# mRo_CANnode_V1_R1.net
KiCad netlist of a schematic drawn in Altium Designer
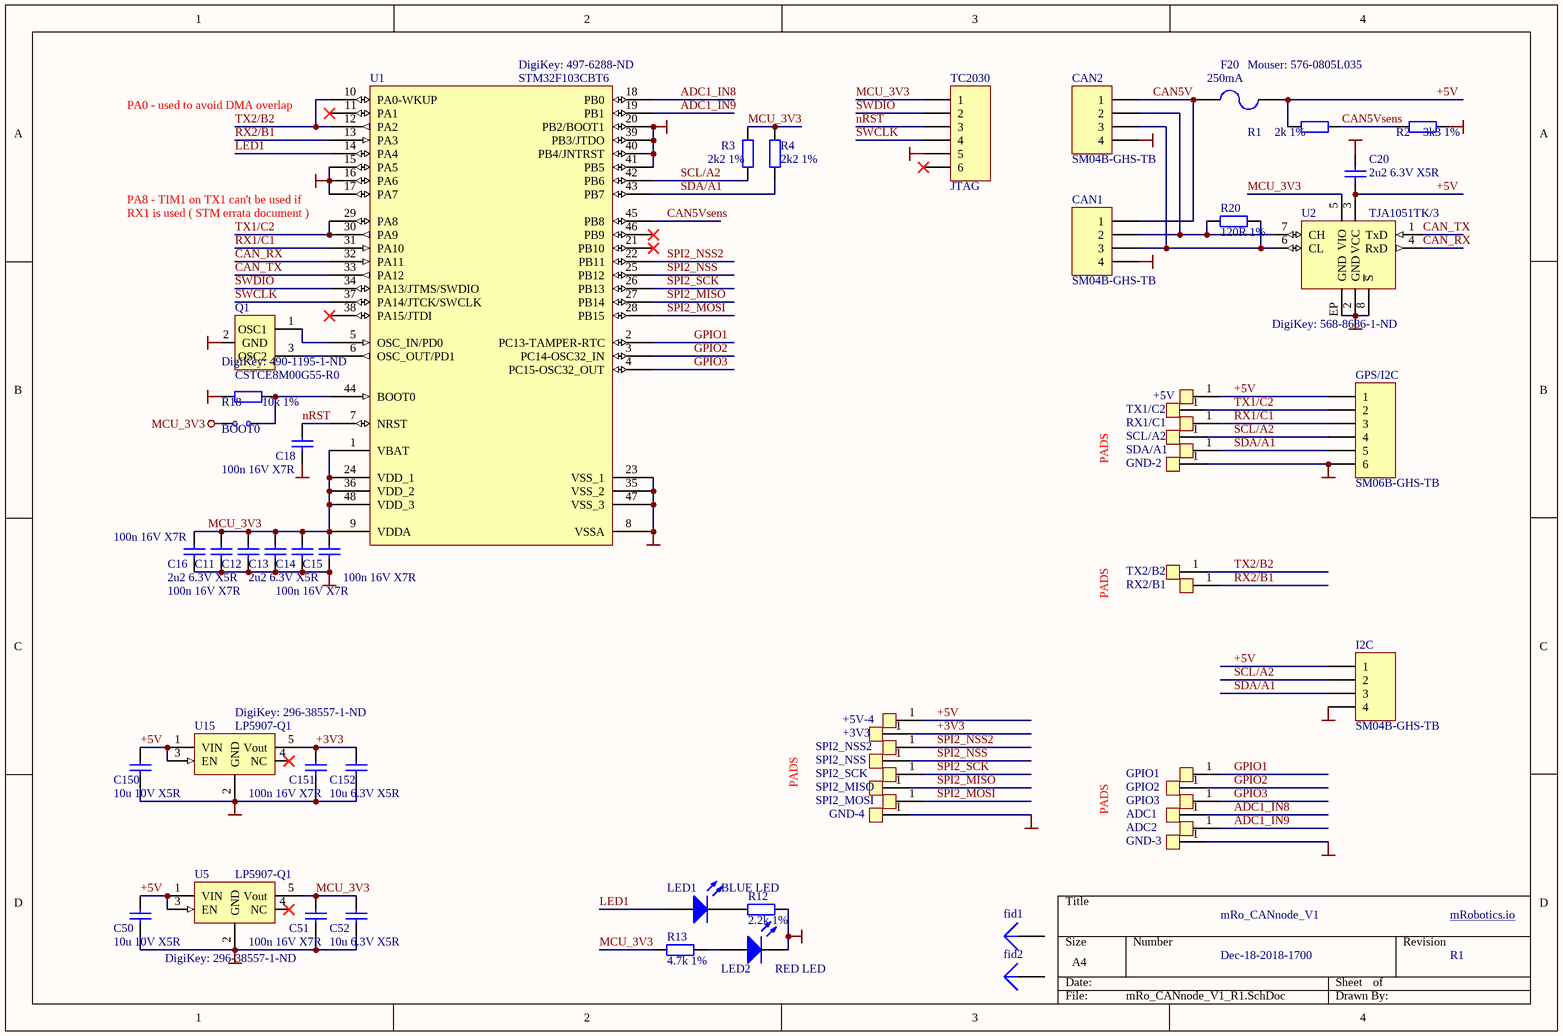
[diagram p0: mRo_CANnode_V1_R1.SchDoc]

(export (version "E")
  (design (tool "Eeschema 10.0.6"))
  (components
    (comp (ref "+3V3")
      (value "+5V")
      (footprint "SMD_TEST_PAD")
      (libsource (lib "My_Altium") (part "Test pad"))
    )
    (comp (ref "+5V")
      (value "+5V")
      (footprint "SMD_TEST_PAD")
      (libsource (lib "My_Altium") (part "Test pad"))
    )
    (comp (ref "+5V-4")
      (value "+5V")
      (footprint "SMD_TEST_PAD")
      (libsource (lib "My_Altium") (part "Test pad"))
    )
    (comp (ref "ADC1")
      (value "GND")
      (footprint "SMD_TEST_PAD")
      (libsource (lib "My_Altium") (part "Test pad"))
    )
    (comp (ref "ADC2")
      (value "GND")
      (footprint "SMD_TEST_PAD")
      (libsource (lib "My_Altium") (part "Test pad"))
    )
    (comp (ref "BOOT0") (value "BLOB") (footprint "BLOB 2") (libsource (lib "My_Altium") (part "BLOB")))
    (comp (ref "C11")
      (value "100n 16V X7R")
      (footprint "0402A")
      (description "Capacitor")
      (fields (field (name "PUBLISHER") "Altium Limited"))
      (libsource (lib "Miscellaneous Devices") (part "Cap"))
    )
    (comp (ref "C12")
      (value "2u2 6.3V X5R")
      (footprint "0402A")
      (description "Capacitor")
      (fields (field (name "PUBLISHER") "Altium Limited"))
      (libsource (lib "Miscellaneous Devices") (part "Cap"))
    )
    (comp (ref "C13")
      (value "2u2 6.3V X5R")
      (footprint "0402A")
      (description "Capacitor")
      (fields (field (name "PUBLISHER") "Altium Limited"))
      (libsource (lib "Miscellaneous Devices") (part "Cap"))
    )
    (comp (ref "C14")
      (value "100n 16V X7R")
      (footprint "0402A")
      (description "Capacitor")
      (fields (field (name "PUBLISHER") "Altium Limited"))
      (libsource (lib "Miscellaneous Devices") (part "Cap"))
    )
    (comp (ref "C15")
      (value "100n 16V X7R")
      (footprint "0402A")
      (description "Capacitor")
      (fields (field (name "PUBLISHER") "Altium Limited"))
      (libsource (lib "Miscellaneous Devices") (part "Cap"))
    )
    (comp (ref "C16")
      (value "100n 16V X7R")
      (footprint "0402A")
      (description "Capacitor")
      (fields (field (name "PUBLISHER") "Altium Limited"))
      (libsource (lib "Miscellaneous Devices") (part "Cap"))
    )
    (comp (ref "C18")
      (value "100n 16V X7R")
      (footprint "0402A")
      (description "Capacitor")
      (fields (field (name "PUBLISHER") "Altium Limited"))
      (libsource (lib "Miscellaneous Devices") (part "Cap"))
    )
    (comp (ref "C20")
      (value "2u2 6.3V X5R")
      (footprint "0402A")
      (description "Capacitor")
      (fields (field (name "PUBLISHER") "Altium Limited"))
      (libsource (lib "Miscellaneous Devices") (part "Cap"))
    )
    (comp (ref "C50")
      (value "10u 10V X5R")
      (footprint "0603A")
      (description "Capacitor")
      (fields (field (name "PUBLISHER") "Altium Limited"))
      (libsource (lib "Miscellaneous Devices") (part "Cap"))
    )
    (comp (ref "C51")
      (value "100n 16V X7R")
      (footprint "0603A")
      (description "Capacitor")
      (fields (field (name "PUBLISHER") "Altium Limited"))
      (libsource (lib "Miscellaneous Devices") (part "Cap"))
    )
    (comp (ref "C52")
      (value "10u 6.3V X5R")
      (footprint "0603A")
      (description "Capacitor")
      (fields (field (name "PUBLISHER") "Altium Limited"))
      (libsource (lib "Miscellaneous Devices") (part "Cap"))
    )
    (comp (ref "C150")
      (value "10u 10V X5R")
      (footprint "0603A")
      (description "Capacitor")
      (fields (field (name "PUBLISHER") "Altium Limited"))
      (libsource (lib "Miscellaneous Devices") (part "Cap"))
    )
    (comp (ref "C151")
      (value "100n 16V X7R")
      (footprint "0603A")
      (description "Capacitor")
      (fields (field (name "PUBLISHER") "Altium Limited"))
      (libsource (lib "Miscellaneous Devices") (part "Cap"))
    )
    (comp (ref "C152")
      (value "10u 6.3V X5R")
      (footprint "0603A")
      (description "Capacitor")
      (fields (field (name "PUBLISHER") "Altium Limited"))
      (libsource (lib "Miscellaneous Devices") (part "Cap"))
    )
    (comp (ref "CAN1")
      (value "SM04B-GHS-TB")
      (footprint "SM04B-GHS-TB")
      (description "Header, 4-Pin")
      (fields (field (name "PUBLISHER") "Altium Limited"))
      (libsource (lib "") (part "Header 4_1"))
    )
    (comp (ref "CAN2")
      (value "SM04B-GHS-TB")
      (footprint "SM04B-GHS-TB")
      (description "Header, 4-Pin")
      (fields (field (name "PUBLISHER") "Altium Limited"))
      (libsource (lib "") (part "Header 4_1"))
    )
    (comp (ref "F20")
      (value "250mA")
      (footprint "0805A")
      (description "Fuse")
      (fields
        (field (name "MANUFACTURER") "Generic Components")
        (field (name "MOUSER") "576-0805L035")
        (field (name "PUBLISHER") "Altium Hobart Technology Centre")
      )
      (libsource (lib "Miscellaneous Devices") (part "Fuse 2"))
    )
    (comp (ref "fid1")
      (value "~")
      (footprint "SMT_PAD")
      (description "Plug")
      (fields (field (name "PUBLISHER") "Altium Limited"))
      (libsource (lib "Miscellaneous Connectors") (part "Plug"))
    )
    (comp (ref "fid2")
      (value "~")
      (footprint "SMT_PAD")
      (description "Plug")
      (fields (field (name "PUBLISHER") "Altium Limited"))
      (libsource (lib "Miscellaneous Connectors") (part "Plug"))
    )
    (comp (ref "GND-2")
      (value "GND")
      (footprint "SMD_TEST_PAD")
      (libsource (lib "My_Altium") (part "Test pad"))
    )
    (comp (ref "GND-3")
      (value "GND")
      (footprint "SMD_TEST_PAD")
      (libsource (lib "My_Altium") (part "Test pad"))
    )
    (comp (ref "GND-4")
      (value "GND")
      (footprint "SMD_TEST_PAD")
      (libsource (lib "My_Altium") (part "Test pad"))
    )
    (comp (ref "GPIO1")
      (value "GPIO1")
      (footprint "SMD_TEST_PAD")
      (libsource (lib "My_Altium") (part "Test pad"))
    )
    (comp (ref "GPIO2")
      (value "GPIO2")
      (footprint "SMD_TEST_PAD")
      (libsource (lib "My_Altium") (part "Test pad"))
    )
    (comp (ref "GPIO3")
      (value "GPIO3")
      (footprint "SMD_TEST_PAD")
      (libsource (lib "My_Altium") (part "Test pad"))
    )
    (comp (ref "GPS/I2C")
      (value "SM06B-GHS-TB")
      (footprint "SM06B-GHS-TB")
      (description "Header, 6-Pin")
      (fields (field (name "PUBLISHER") "Altium Limited"))
      (libsource (lib "Miscellaneous Connectors") (part "Header 6"))
    )
    (comp (ref "I2C")
      (value "SM04B-GHS-TB")
      (footprint "SM04B-GHS-TB")
      (description "Header, 4-Pin")
      (fields (field (name "PUBLISHER") "Altium Limited"))
      (libsource (lib "Miscellaneous Connectors") (part "Header 4"))
    )
    (comp (ref "LED1")
      (value "BLUE LED")
      (footprint "0603A")
      (description "Typical INFRARED GaAs LED")
      (fields (field (name "PUBLISHER") "Altium Limited"))
      (libsource (lib "Miscellaneous Devices") (part "LED0"))
    )
    (comp (ref "LED2")
      (value "RED LED")
      (footprint "0603A")
      (description "Typical INFRARED GaAs LED")
      (fields (field (name "PUBLISHER") "Altium Limited"))
      (libsource (lib "Miscellaneous Devices") (part "LED0"))
    )
    (comp (ref "Q1")
      (value "CSTCE8M00G55-R0")
      (footprint "CERALOCK_RES")
      (fields (field (name "DIGIKEY") "490-1195-1-ND"))
      (libsource (lib "My_Altium") (part "CERAMIC_RESONATOR_3PIN"))
    )
    (comp (ref "R1")
      (value "2k 1%")
      (footprint "0402A")
      (description "Resistor")
      (fields (field (name "PUBLISHER") "Altium Limited"))
      (libsource (lib "Miscellaneous Devices") (part "Res2"))
    )
    (comp (ref "R2")
      (value "3k3 1%")
      (footprint "0402A")
      (description "Resistor")
      (fields (field (name "PUBLISHER") "Altium Limited"))
      (libsource (lib "Miscellaneous Devices") (part "Res2"))
    )
    (comp (ref "R3")
      (value "2k2 1%")
      (footprint "0402A")
      (description "Resistor")
      (fields (field (name "PUBLISHER") "Altium Limited"))
      (libsource (lib "") (part "Res2_1"))
    )
    (comp (ref "R4")
      (value "2k2 1%")
      (footprint "0402A")
      (description "Resistor")
      (fields (field (name "PUBLISHER") "Altium Limited"))
      (libsource (lib "") (part "Res2_1"))
    )
    (comp (ref "R12")
      (value "2.2k 1%")
      (footprint "0402A")
      (description "Resistor")
      (fields (field (name "PUBLISHER") "Altium Limited"))
      (libsource (lib "Miscellaneous Devices") (part "Res2"))
    )
    (comp (ref "R13")
      (value "4.7k 1%")
      (footprint "0603A")
      (description "Resistor")
      (fields (field (name "PUBLISHER") "Altium Limited"))
      (libsource (lib "Miscellaneous Devices") (part "Res2"))
    )
    (comp (ref "R18")
      (value "10k 1%")
      (footprint "0402A")
      (description "Resistor")
      (fields (field (name "PUBLISHER") "Altium Limited"))
      (libsource (lib "Miscellaneous Devices") (part "Res2"))
    )
    (comp (ref "R20")
      (value "120R 1%")
      (footprint "0603A")
      (description "Resistor")
      (fields (field (name "PUBLISHER") "Altium Limited"))
      (libsource (lib "Miscellaneous Devices") (part "Res2"))
    )
    (comp (ref "RX1/C1")
      (value "RX1/TLM/C1")
      (footprint "SMD_TEST_PAD")
      (libsource (lib "My_Altium") (part "Test pad"))
    )
    (comp (ref "RX2/B1")
      (value "RX2/B1")
      (footprint "SMD_TEST_PAD")
      (libsource (lib "My_Altium") (part "Test pad"))
    )
    (comp (ref "SCL/A2")
      (value "SDA")
      (footprint "SMD_TEST_PAD")
      (libsource (lib "My_Altium") (part "Test pad"))
    )
    (comp (ref "SDA/A1")
      (value "SDA/A1")
      (footprint "SMD_TEST_PAD")
      (libsource (lib "My_Altium") (part "Test pad"))
    )
    (comp (ref "SPI2_MISO")
      (value "SPI2_MISO")
      (footprint "SMD_TEST_PAD")
      (libsource (lib "My_Altium") (part "Test pad"))
    )
    (comp (ref "SPI2_MOSI")
      (value "SPI2_MOSI")
      (footprint "SMD_TEST_PAD")
      (libsource (lib "My_Altium") (part "Test pad"))
    )
    (comp (ref "SPI2_NSS")
      (value "SPI2_NSS")
      (footprint "SMD_TEST_PAD")
      (libsource (lib "My_Altium") (part "Test pad"))
    )
    (comp (ref "SPI2_NSS2")
      (value "SPI2_NSS2")
      (footprint "SMD_TEST_PAD")
      (libsource (lib "My_Altium") (part "Test pad"))
    )
    (comp (ref "SPI2_SCK")
      (value "SPI2_SCK")
      (footprint "SMD_TEST_PAD")
      (libsource (lib "My_Altium") (part "Test pad"))
    )
    (comp (ref "TC2030")
      (value "JTAG")
      (footprint "JTAG_TC2030")
      (description "Header, 6-Pin")
      (fields (field (name "PUBLISHER") "Altium Limited"))
      (libsource (lib "Miscellaneous Connectors") (part "Header 6"))
    )
    (comp (ref "TX1/C2")
      (value "VDD_USB")
      (footprint "SMD_TEST_PAD")
      (libsource (lib "My_Altium") (part "Test pad"))
    )
    (comp (ref "TX2/B2")
      (value "TX2/B2")
      (footprint "SMD_TEST_PAD")
      (libsource (lib "My_Altium") (part "Test pad"))
    )
    (comp (ref "U1")
      (value "STM32F103CBT6")
      (footprint "LQFP48_N")
      (description "STM32 ARM-based 32-bit MCU with 128 Kbytes Flash, 48-pin LQFP, Industrial Temperature")
      (fields (field (name "DIGIKEY") "497-6288-ND") (field (name "PUBLISHER") "Altium Limited"))
      (libsource (lib "ST Microcontroller 32-Bit STM32") (part "STM32F103CBT6"))
    )
    (comp (ref "U2")
      (value "TJA1051TK/3")
      (footprint "8DFN_3x3")
      (fields (field (name "DIGIKEY") "568-8686-1-ND"))
      (libsource (lib "My_Altium") (part "TJA1051T"))
    )
    (comp (ref "U5")
      (value "LP5907-Q1")
      (footprint "SOT23-5")
      (fields (field (name "DIGIKEY") "296-38557-1-ND"))
      (libsource (lib "My_Altium") (part "LP5907-Q1"))
    )
    (comp (ref "U15")
      (value "LP5907-Q1")
      (footprint "SOT23-5")
      (fields (field (name "DIGIKEY") "296-38557-1-ND"))
      (libsource (lib "My_Altium") (part "LP5907-Q1"))
    )
  )
  (nets
    (net (code "1") (name "/+3V3") (class "Default")
      (node (ref "+3V3") (pin "1") (pintype "passive"))
      (node (ref "C151") (pin "2") (pinfunction "2_2") (pintype "passive"))
      (node (ref "C152") (pin "2") (pinfunction "2_2") (pintype "passive"))
      (node (ref "U15") (pin "5") (pinfunction "Vout_5") (pintype "power_in"))
    )
    (net (code "2") (name "/+5V") (class "Default")
      (node (ref "+5V") (pin "1") (pintype "passive"))
      (node (ref "+5V-4") (pin "1") (pintype "passive"))
      (node (ref "C150") (pin "2") (pinfunction "2_2") (pintype "passive"))
      (node (ref "C20") (pin "2") (pinfunction "2_2") (pintype "passive"))
      (node (ref "C50") (pin "2") (pinfunction "2_2") (pintype "passive"))
      (node (ref "F20") (pin "2") (pinfunction "2_2") (pintype "passive"))
      (node (ref "GPS/I2C") (pin "1") (pinfunction "1_1") (pintype "passive"))
      (node (ref "I2C") (pin "1") (pinfunction "1_1") (pintype "passive"))
      (node (ref "R1") (pin "2") (pinfunction "2_2") (pintype "passive"))
      (node (ref "U15") (pin "1") (pinfunction "VIN_1") (pintype "power_in"))
      (node (ref "U15") (pin "3") (pinfunction "EN_3") (pintype "input"))
      (node (ref "U2") (pin "3") (pinfunction "VCC_3") (pintype "power_in"))
      (node (ref "U5") (pin "1") (pinfunction "VIN_1") (pintype "power_in"))
      (node (ref "U5") (pin "3") (pinfunction "EN_3") (pintype "input"))
    )
    (net (code "3") (name "/ADC1_IN8") (class "Default")
      (node (ref "ADC1") (pin "1") (pintype "passive"))
      (node (ref "U1") (pin "18") (pinfunction "PB0_18") (pintype "bidirectional"))
    )
    (net (code "4") (name "/ADC1_IN9") (class "Default")
      (node (ref "ADC2") (pin "1") (pintype "passive"))
      (node (ref "U1") (pin "19") (pinfunction "PB1_19") (pintype "bidirectional"))
    )
    (net (code "5") (name "/CAN5V") (class "Default")
      (node (ref "CAN1") (pin "1") (pinfunction "1_1") (pintype "passive"))
      (node (ref "CAN2") (pin "1") (pinfunction "1_1") (pintype "passive"))
      (node (ref "F20") (pin "1") (pinfunction "1_1") (pintype "passive"))
    )
    (net (code "6") (name "/CAN5Vsens") (class "Default")
      (node (ref "R1") (pin "1") (pinfunction "1_1") (pintype "passive"))
      (node (ref "R2") (pin "2") (pinfunction "2_2") (pintype "passive"))
      (node (ref "U1") (pin "45") (pinfunction "PB8_45") (pintype "bidirectional"))
    )
    (net (code "7") (name "/CAN_RX") (class "Default")
      (node (ref "U1") (pin "32") (pinfunction "PA11_32") (pintype "input"))
      (node (ref "U2") (pin "4") (pinfunction "RxD_4") (pintype "output"))
    )
    (net (code "8") (name "/CAN_TX") (class "Default")
      (node (ref "U1") (pin "33") (pinfunction "PA12_33") (pintype "output"))
      (node (ref "U2") (pin "1") (pinfunction "TxD_1") (pintype "input"))
    )
    (net (code "9") (name "/GPIO1") (class "Default")
      (node (ref "GPIO1") (pin "1") (pintype "passive"))
      (node (ref "U1") (pin "2") (pinfunction "PC13-TAMPER-RTC_2") (pintype "bidirectional"))
    )
    (net (code "10") (name "/GPIO2") (class "Default")
      (node (ref "GPIO2") (pin "1") (pintype "passive"))
      (node (ref "U1") (pin "3") (pinfunction "PC14-OSC32_IN_3") (pintype "bidirectional"))
    )
    (net (code "11") (name "/GPIO3") (class "Default")
      (node (ref "GPIO3") (pin "1") (pintype "passive"))
      (node (ref "U1") (pin "4") (pinfunction "PC15-OSC32_OUT_4") (pintype "bidirectional"))
    )
    (net (code "12") (name "/LED1") (class "Default")
      (node (ref "LED1") (pin "1") (pinfunction "A_1") (pintype "passive"))
      (node (ref "U1") (pin "14") (pinfunction "PA4_14") (pintype "bidirectional"))
    )
    (net (code "13") (name "/RX1{slash}C1") (class "Default")
      (node (ref "GPS/I2C") (pin "3") (pinfunction "3_3") (pintype "passive"))
      (node (ref "RX1/C1") (pin "1") (pintype "passive"))
      (node (ref "U1") (pin "31") (pinfunction "PA10_31") (pintype "input"))
    )
    (net (code "14") (name "/RX2{slash}B1") (class "Default")
      (node (ref "RX2/B1") (pin "1") (pintype "passive"))
      (node (ref "U1") (pin "13") (pinfunction "PA3_13") (pintype "input"))
    )
    (net (code "15") (name "/SCL{slash}A2") (class "Default")
      (node (ref "GPS/I2C") (pin "4") (pinfunction "4_4") (pintype "passive"))
      (node (ref "I2C") (pin "2") (pinfunction "2_2") (pintype "passive"))
      (node (ref "R3") (pin "2") (pinfunction "2_2") (pintype "passive"))
      (node (ref "SCL/A2") (pin "1") (pintype "passive"))
      (node (ref "U1") (pin "42") (pinfunction "PB6_42") (pintype "bidirectional"))
    )
    (net (code "16") (name "/SDA{slash}A1") (class "Default")
      (node (ref "GPS/I2C") (pin "5") (pinfunction "5_5") (pintype "passive"))
      (node (ref "I2C") (pin "3") (pinfunction "3_3") (pintype "passive"))
      (node (ref "R4") (pin "2") (pinfunction "2_2") (pintype "passive"))
      (node (ref "SDA/A1") (pin "1") (pintype "passive"))
      (node (ref "U1") (pin "43") (pinfunction "PB7_43") (pintype "bidirectional"))
    )
    (net (code "17") (name "/SPI2_MISO") (class "Default")
      (node (ref "SPI2_MISO") (pin "1") (pintype "passive"))
      (node (ref "U1") (pin "27") (pinfunction "PB14_27") (pintype "bidirectional"))
    )
    (net (code "18") (name "/SPI2_MOSI") (class "Default")
      (node (ref "SPI2_MOSI") (pin "1") (pintype "passive"))
      (node (ref "U1") (pin "28") (pinfunction "PB15_28") (pintype "bidirectional"))
    )
    (net (code "19") (name "/SPI2_NSS") (class "Default")
      (node (ref "SPI2_NSS") (pin "1") (pintype "passive"))
      (node (ref "U1") (pin "25") (pinfunction "PB12_25") (pintype "bidirectional"))
    )
    (net (code "20") (name "/SPI2_NSS2") (class "Default")
      (node (ref "SPI2_NSS2") (pin "1") (pintype "passive"))
      (node (ref "U1") (pin "22") (pinfunction "PB11_22") (pintype "bidirectional"))
    )
    (net (code "21") (name "/SPI2_SCK") (class "Default")
      (node (ref "SPI2_SCK") (pin "1") (pintype "passive"))
      (node (ref "U1") (pin "26") (pinfunction "PB13_26") (pintype "bidirectional"))
    )
    (net (code "22") (name "/SWCLK") (class "Default")
      (node (ref "TC2030") (pin "4") (pinfunction "4_4") (pintype "passive"))
      (node (ref "U1") (pin "37") (pinfunction "PA14/JTCK/SWCLK_37") (pintype "bidirectional"))
    )
    (net (code "23") (name "/SWDIO") (class "Default")
      (node (ref "TC2030") (pin "2") (pinfunction "2_2") (pintype "passive"))
      (node (ref "U1") (pin "34") (pinfunction "PA13/JTMS/SWDIO_34") (pintype "bidirectional"))
    )
    (net (code "24") (name "/TX1{slash}C2") (class "Default")
      (node (ref "GPS/I2C") (pin "2") (pinfunction "2_2") (pintype "passive"))
      (node (ref "TX1/C2") (pin "1") (pintype "passive"))
      (node (ref "U1") (pin "29") (pinfunction "PA8_29") (pintype "bidirectional"))
      (node (ref "U1") (pin "30") (pinfunction "PA9_30") (pintype "output"))
    )
    (net (code "25") (name "/TX2{slash}B2") (class "Default")
      (node (ref "TX2/B2") (pin "1") (pintype "passive"))
      (node (ref "U1") (pin "10") (pinfunction "PA0-WKUP_10") (pintype "bidirectional"))
      (node (ref "U1") (pin "12") (pinfunction "PA2_12") (pintype "output"))
    )
    (net (code "26") (name "/nRST") (class "Default")
      (node (ref "C18") (pin "2") (pinfunction "2_2") (pintype "passive"))
      (node (ref "TC2030") (pin "3") (pinfunction "3_3") (pintype "passive"))
      (node (ref "U1") (pin "7") (pinfunction "NRST_7") (pintype "bidirectional"))
    )
    (net (code "27") (name "GND") (class "Default")
      (node (ref "C11") (pin "1") (pinfunction "1_1") (pintype "passive"))
      (node (ref "C12") (pin "1") (pinfunction "1_1") (pintype "passive"))
      (node (ref "C13") (pin "1") (pinfunction "1_1") (pintype "passive"))
      (node (ref "C14") (pin "1") (pinfunction "1_1") (pintype "passive"))
      (node (ref "C15") (pin "1") (pinfunction "1_1") (pintype "passive"))
      (node (ref "C150") (pin "1") (pinfunction "1_1") (pintype "passive"))
      (node (ref "C151") (pin "1") (pinfunction "1_1") (pintype "passive"))
      (node (ref "C152") (pin "1") (pinfunction "1_1") (pintype "passive"))
      (node (ref "C16") (pin "1") (pinfunction "1_1") (pintype "passive"))
      (node (ref "C18") (pin "1") (pinfunction "1_1") (pintype "passive"))
      (node (ref "C20") (pin "1") (pinfunction "1_1") (pintype "passive"))
      (node (ref "C50") (pin "1") (pinfunction "1_1") (pintype "passive"))
      (node (ref "C51") (pin "1") (pinfunction "1_1") (pintype "passive"))
      (node (ref "C52") (pin "1") (pinfunction "1_1") (pintype "passive"))
      (node (ref "CAN1") (pin "4") (pinfunction "4_4") (pintype "passive"))
      (node (ref "CAN2") (pin "4") (pinfunction "4_4") (pintype "passive"))
      (node (ref "GND-2") (pin "1") (pintype "passive"))
      (node (ref "GND-3") (pin "1") (pintype "passive"))
      (node (ref "GND-4") (pin "1") (pintype "passive"))
      (node (ref "GPS/I2C") (pin "6") (pinfunction "6_6") (pintype "passive"))
      (node (ref "I2C") (pin "4") (pinfunction "4_4") (pintype "passive"))
      (node (ref "LED2") (pin "2") (pinfunction "K_2") (pintype "passive"))
      (node (ref "Q1") (pin "2") (pinfunction "GND_2") (pintype "power_in"))
      (node (ref "R12") (pin "1") (pinfunction "1_1") (pintype "passive"))
      (node (ref "R18") (pin "2") (pinfunction "2_2") (pintype "passive"))
      (node (ref "R2") (pin "1") (pinfunction "1_1") (pintype "passive"))
      (node (ref "TC2030") (pin "5") (pinfunction "5_5") (pintype "passive"))
      (node (ref "U1") (pin "15") (pinfunction "PA5_15") (pintype "bidirectional"))
      (node (ref "U1") (pin "16") (pinfunction "PA6_16") (pintype "bidirectional"))
      (node (ref "U1") (pin "17") (pinfunction "PA7_17") (pintype "bidirectional"))
      (node (ref "U1") (pin "20") (pinfunction "PB2/BOOT1_20") (pintype "bidirectional"))
      (node (ref "U1") (pin "23") (pinfunction "VSS_1_23") (pintype "power_in"))
      (node (ref "U1") (pin "35") (pinfunction "VSS_2_35") (pintype "power_in"))
      (node (ref "U1") (pin "39") (pinfunction "PB3/JTDO_39") (pintype "bidirectional"))
      (node (ref "U1") (pin "40") (pinfunction "PB4/JNTRST_40") (pintype "bidirectional"))
      (node (ref "U1") (pin "41") (pinfunction "PB5_41") (pintype "bidirectional"))
      (node (ref "U1") (pin "47") (pinfunction "VSS_3_47") (pintype "power_in"))
      (node (ref "U1") (pin "8") (pinfunction "VSSA_8") (pintype "power_in"))
      (node (ref "U15") (pin "2") (pinfunction "GND_2") (pintype "power_in"))
      (node (ref "U2") (pin "2") (pinfunction "GND_2") (pintype "power_in"))
      (node (ref "U2") (pin "8") (pinfunction "~{S}_8") (pintype "passive"))
      (node (ref "U2") (pin "EP") (pinfunction "GND_EP") (pintype "power_in"))
      (node (ref "U5") (pin "2") (pinfunction "GND_2") (pintype "power_in"))
    )
    (net (code "28") (name "MCU_3V3") (class "Default")
      (node (ref "BOOT0") (pin "1") (pinfunction "1_1") (pintype "passive"))
      (node (ref "C11") (pin "2") (pinfunction "2_2") (pintype "passive"))
      (node (ref "C12") (pin "2") (pinfunction "2_2") (pintype "passive"))
      (node (ref "C13") (pin "2") (pinfunction "2_2") (pintype "passive"))
      (node (ref "C14") (pin "2") (pinfunction "2_2") (pintype "passive"))
      (node (ref "C15") (pin "2") (pinfunction "2_2") (pintype "passive"))
      (node (ref "C16") (pin "2") (pinfunction "2_2") (pintype "passive"))
      (node (ref "C51") (pin "2") (pinfunction "2_2") (pintype "passive"))
      (node (ref "C52") (pin "2") (pinfunction "2_2") (pintype "passive"))
      (node (ref "R13") (pin "2") (pinfunction "2_2") (pintype "passive"))
      (node (ref "R3") (pin "1") (pinfunction "1_1") (pintype "passive"))
      (node (ref "R4") (pin "1") (pinfunction "1_1") (pintype "passive"))
      (node (ref "TC2030") (pin "1") (pinfunction "1_1") (pintype "passive"))
      (node (ref "U1") (pin "1") (pinfunction "VBAT_1") (pintype "power_in"))
      (node (ref "U1") (pin "24") (pinfunction "VDD_1_24") (pintype "power_in"))
      (node (ref "U1") (pin "36") (pinfunction "VDD_2_36") (pintype "power_in"))
      (node (ref "U1") (pin "48") (pinfunction "VDD_3_48") (pintype "power_in"))
      (node (ref "U1") (pin "9") (pinfunction "VDDA_9") (pintype "power_in"))
      (node (ref "U2") (pin "5") (pinfunction "VIO_5") (pintype "power_in"))
      (node (ref "U5") (pin "5") (pinfunction "Vout_5") (pintype "power_in"))
    )
    (net (code "29") (name "Net-(LED1-K)") (class "Default")
      (node (ref "LED1") (pin "2") (pinfunction "K_2") (pintype "passive"))
      (node (ref "R12") (pin "2") (pinfunction "2_2") (pintype "passive"))
    )
    (net (code "30") (name "Net-(LED2-A)") (class "Default")
      (node (ref "LED2") (pin "1") (pinfunction "A_1") (pintype "passive"))
      (node (ref "R13") (pin "1") (pinfunction "1_1") (pintype "passive"))
    )
    (net (code "31") (name "Net-(Q1-OSC1)") (class "Default")
      (node (ref "Q1") (pin "1") (pinfunction "OSC1_1") (pintype "passive"))
      (node (ref "U1") (pin "5") (pinfunction "OSC_IN/PD0_5") (pintype "input"))
    )
    (net (code "32") (name "Net-(Q1-OSC2)") (class "Default")
      (node (ref "Q1") (pin "3") (pinfunction "OSC2_3") (pintype "passive"))
      (node (ref "U1") (pin "6") (pinfunction "OSC_OUT/PD1_6") (pintype "output"))
    )
    (net (code "33") (name "Net-(U1-BOOT0)") (class "Default")
      (node (ref "BOOT0") (pin "2") (pinfunction "2_2") (pintype "passive"))
      (node (ref "R18") (pin "1") (pinfunction "1_1") (pintype "passive"))
      (node (ref "U1") (pin "44") (pinfunction "BOOT0_44") (pintype "input"))
    )
    (net (code "34") (name "Net-(U2-CH)") (class "Default")
      (node (ref "CAN1") (pin "2") (pinfunction "2_2") (pintype "passive"))
      (node (ref "CAN2") (pin "2") (pinfunction "2_2") (pintype "passive"))
      (node (ref "R20") (pin "2") (pinfunction "2_2") (pintype "passive"))
      (node (ref "U2") (pin "7") (pinfunction "CH_7") (pintype "bidirectional"))
    )
    (net (code "35") (name "Net-(U2-CL)") (class "Default")
      (node (ref "CAN1") (pin "3") (pinfunction "3_3") (pintype "passive"))
      (node (ref "CAN2") (pin "3") (pinfunction "3_3") (pintype "passive"))
      (node (ref "R20") (pin "1") (pinfunction "1_1") (pintype "passive"))
      (node (ref "U2") (pin "6") (pinfunction "CL_6") (pintype "bidirectional"))
    )
    (net (code "36") (name "unconnected-(TC2030-Pad6)") (class "Default")
      (node (ref "TC2030") (pin "6") (pinfunction "6_6") (pintype "passive+no_connect"))
    )
    (net (code "37") (name "unconnected-(U1-PA1-Pad11)") (class "Default")
      (node (ref "U1") (pin "11") (pinfunction "PA1_11") (pintype "bidirectional+no_connect"))
    )
    (net (code "38") (name "unconnected-(U1-PA15{slash}JTDI-Pad38)") (class "Default")
      (node (ref "U1") (pin "38") (pinfunction "PA15/JTDI_38") (pintype "bidirectional+no_connect"))
    )
    (net (code "39") (name "unconnected-(U1-PB9-Pad46)") (class "Default")
      (node (ref "U1") (pin "46") (pinfunction "PB9_46") (pintype "bidirectional+no_connect"))
    )
    (net (code "40") (name "unconnected-(U1-PB10-Pad21)") (class "Default")
      (node (ref "U1") (pin "21") (pinfunction "PB10_21") (pintype "bidirectional+no_connect"))
    )
    (net (code "41") (name "unconnected-(U5-NC-Pad4)") (class "Default")
      (node (ref "U5") (pin "4") (pinfunction "NC_4") (pintype "passive+no_connect"))
    )
    (net (code "42") (name "unconnected-(U15-NC-Pad4)") (class "Default")
      (node (ref "U15") (pin "4") (pinfunction "NC_4") (pintype "passive+no_connect"))
    )
    (net (code "43") (name "unconnected-(fid1-Pad1)") (class "Default")
      (node (ref "fid1") (pin "1") (pinfunction "1_1") (pintype "passive"))
    )
    (net (code "44") (name "unconnected-(fid2-Pad1)") (class "Default")
      (node (ref "fid2") (pin "1") (pinfunction "1_1") (pintype "passive"))
    )
  )
)
